# Sch_sensors.net
KiCad netlist of a schematic drawn in Altium Designer
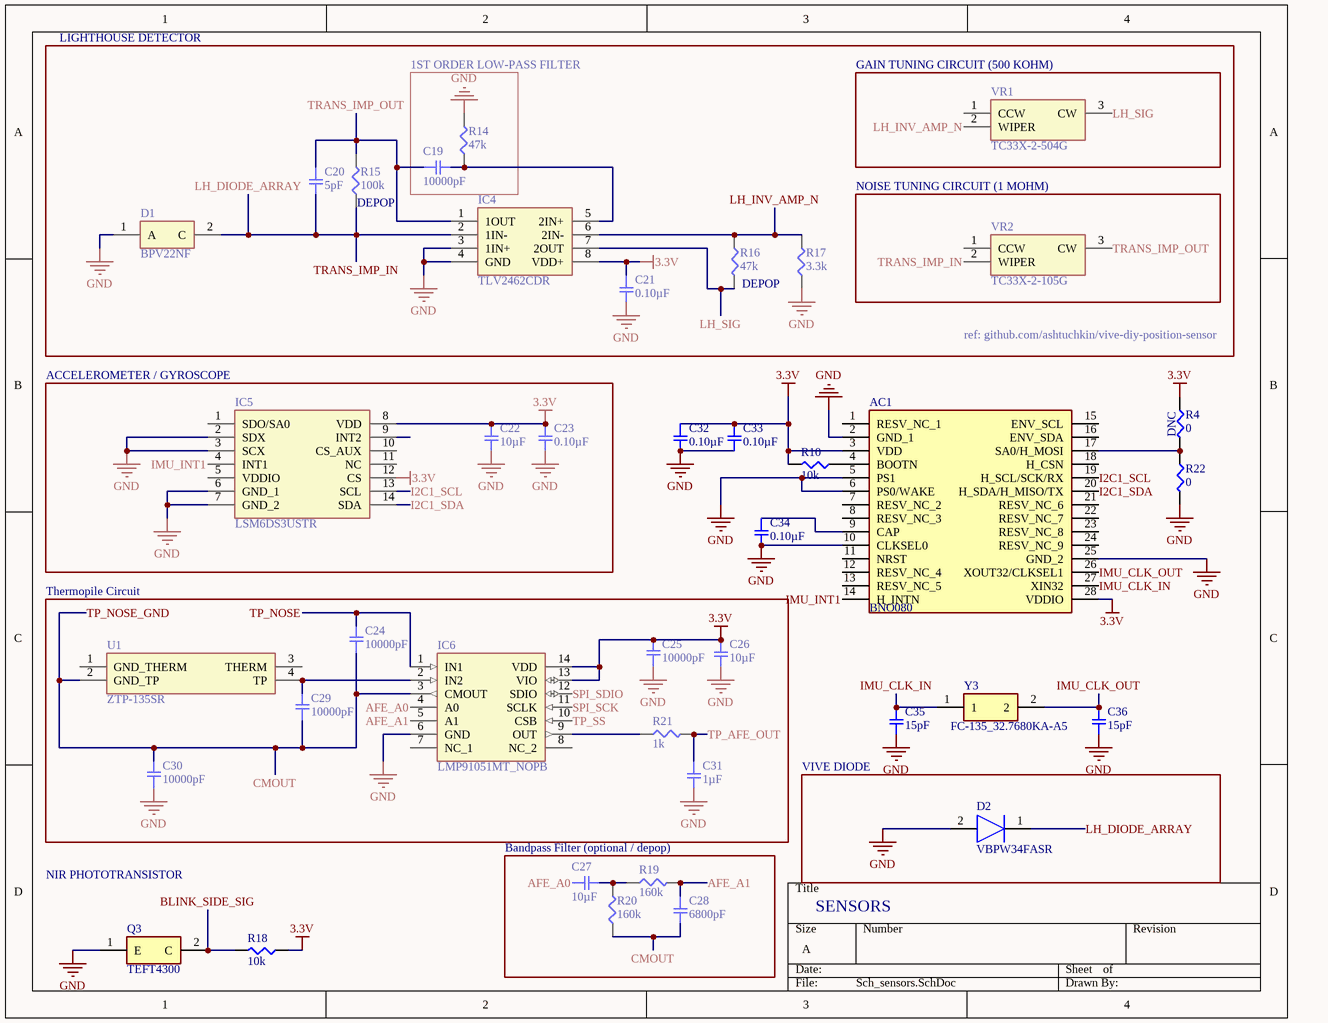
[diagram p0: Sch_sensors.SchDoc]

(export (version "E")
  (design (tool "Eeschema 10.0.6"))
  (components
    (comp (ref "AC1")
      (value "BNO080")
      (footprint "SamacSys:BNO080")
      (description "Accelerometer")
      (libsource (lib "*") (part "BNO080"))
    )
    (comp (ref "C19")
      (value "10000pF")
      (footprint "SMD-0402C")
      (description "CAP CER 10000PF 50V X7R 0402")
      (fields
        (field (name "DIGI-KEY PART NUMBER") "490-4762-1-ND")
        (field (name "PART NUMBER") "GCM155R71H103KA55D")
      )
      (libsource (lib "capacitor_murata_0402") (part "GCM155R71H103KA55D"))
    )
    (comp (ref "C20")
      (value "5pF")
      (footprint "SMD-0402C")
      (description "CAP CER 5PF 50V NP0 0402")
      (fields
        (field (name "DIGI-KEY PART NUMBER") "490-8103-1-ND")
        (field (name "PART NUMBER") "GJM1555C1H5R0BB01D")
      )
      (libsource (lib "capacitor_murata_0402") (part "GJM1555C1H5R0BB01D"))
    )
    (comp (ref "C21")
      (value "0.10µF")
      (footprint "SMD-0402C")
      (description "CAP CER 0.1UF 16V X7R 0402")
      (fields
        (field (name "DIGI-KEY PART NUMBER") "490-4759-1-ND")
        (field (name "PART NUMBER") "GCM155R71C104KA55D")
      )
      (libsource (lib "capacitor_murata_0402") (part "GCM155R71C104KA55D"))
    )
    (comp (ref "C22")
      (value "10µF")
      (footprint "SMD-0402C")
      (description "CAP CER 10UF 6.3V X5R 0402")
      (fields
        (field (name "DIGI-KEY PART NUMBER") "490-13211-1-ND")
        (field (name "PART NUMBER") "GRJ155R60J106ME11D")
      )
      (libsource (lib "capacitor_murata_0402") (part "GRJ155R60J106ME11D"))
    )
    (comp (ref "C23")
      (value "0.10µF")
      (footprint "SMD-0402C")
      (description "CAP CER 0.1UF 16V X7R 0402")
      (fields
        (field (name "DIGI-KEY PART NUMBER") "490-4759-1-ND")
        (field (name "PART NUMBER") "GCM155R71C104KA55D")
      )
      (libsource (lib "capacitor_murata_0402") (part "GCM155R71C104KA55D"))
    )
    (comp (ref "C24")
      (value "10000pF")
      (footprint "SMD-0402C")
      (description "CAP CER 10000PF 50V X7R 0402")
      (fields
        (field (name "DIGI-KEY PART NUMBER") "490-4762-1-ND")
        (field (name "PART NUMBER") "GCM155R71H103KA55D")
      )
      (libsource (lib "capacitor_murata_0402") (part "GCM155R71H103KA55D"))
    )
    (comp (ref "C25")
      (value "10000pF")
      (footprint "SMD-0402C")
      (description "CAP CER 10000PF 50V X7R 0402")
      (fields
        (field (name "DIGI-KEY PART NUMBER") "490-4762-1-ND")
        (field (name "PART NUMBER") "GCM155R71H103KA55D")
      )
      (libsource (lib "capacitor_murata_0402") (part "GCM155R71H103KA55D"))
    )
    (comp (ref "C26")
      (value "10µF")
      (footprint "SMD-0402C")
      (description "CAP CER 10UF 6.3V X5R 0402")
      (fields
        (field (name "DIGI-KEY PART NUMBER") "490-13211-1-ND")
        (field (name "PART NUMBER") "GRJ155R60J106ME11D")
      )
      (libsource (lib "capacitor_murata_0402") (part "GRJ155R60J106ME11D"))
    )
    (comp (ref "C27")
      (value "10µF")
      (footprint "SMD-0402C")
      (description "CAP CER 10UF 6.3V X5R 0402")
      (fields
        (field (name "DIGI-KEY PART NUMBER") "490-13211-1-ND")
        (field (name "PART NUMBER") "GRJ155R60J106ME11D")
      )
      (libsource (lib "capacitor_murata_0402") (part "GRJ155R60J106ME11D"))
    )
    (comp (ref "C28")
      (value "6800pF")
      (footprint "SMD-0402C")
      (description "CAP CER 6800PF 25V X7R 0402")
      (fields
        (field (name "DIGI-KEY PART NUMBER") "490-11422-1-ND")
        (field (name "PART NUMBER") "GRM155R71E682KA01J")
      )
      (libsource (lib "capacitor_murata_0402") (part "GRM155R71E682KA01J"))
    )
    (comp (ref "C29")
      (value "10000pF")
      (footprint "SMD-0402C")
      (description "CAP CER 10000PF 50V X7R 0402")
      (fields
        (field (name "DIGI-KEY PART NUMBER") "490-4762-1-ND")
        (field (name "PART NUMBER") "GCM155R71H103KA55D")
      )
      (libsource (lib "capacitor_murata_0402") (part "GCM155R71H103KA55D"))
    )
    (comp (ref "C30")
      (value "10000pF")
      (footprint "SMD-0402C")
      (description "CAP CER 10000PF 50V X7R 0402")
      (fields
        (field (name "DIGI-KEY PART NUMBER") "490-4762-1-ND")
        (field (name "PART NUMBER") "GCM155R71H103KA55D")
      )
      (libsource (lib "capacitor_murata_0402") (part "GCM155R71H103KA55D"))
    )
    (comp (ref "C31")
      (value "1µF")
      (footprint "SMD-0402C")
      (description "CAP CER 1UF 10V X7S 0402")
      (fields
        (field (name "DIGI-KEY PART NUMBER") "490-13409-1-ND")
        (field (name "PART NUMBER") "GCM155C71A105KE38D")
      )
      (libsource (lib "capacitor_murata_0402") (part "GCM155C71A105KE38D"))
    )
    (comp (ref "C32")
      (value "0.10µF")
      (footprint "CAPC1005X55N")
      (description "CAP CER 0.1UF 16V X7R 0402")
      (fields
        (field (name "DIGI-KEY PART NUMBER") "490-4759-1-ND")
        (field (name "PART NUMBER") "GCM155R71C104KA55D")
      )
      (libsource (lib "capacitor_murata_0402") (part "GCM155R71C104KA55D"))
    )
    (comp (ref "C33")
      (value "0.10µF")
      (footprint "CAPC1005X55N")
      (description "CAP CER 0.1UF 16V X7R 0402")
      (fields
        (field (name "DIGI-KEY PART NUMBER") "490-4759-1-ND")
        (field (name "PART NUMBER") "GCM155R71C104KA55D")
      )
      (libsource (lib "capacitor_murata_0402") (part "GCM155R71C104KA55D"))
    )
    (comp (ref "C34")
      (value "0.10µF")
      (footprint "CAPC1005X55N")
      (description "CAP CER 0.1UF 16V X7R 0402")
      (fields
        (field (name "DIGI-KEY PART NUMBER") "490-4759-1-ND")
        (field (name "PART NUMBER") "GCM155R71C104KA55D")
      )
      (libsource (lib "capacitor_murata_0402") (part "GCM155R71C104KA55D"))
    )
    (comp (ref "C35")
      (value "15pF")
      (footprint "CAPC1005X55N")
      (description "CAP CER 15PF 50V NP0 0402")
      (fields
        (field (name "DIGI-KEY PART NUMBER") "490-11147-1-ND")
        (field (name "PART NUMBER") "GCM1555C1H150JA16D")
      )
      (libsource (lib "capacitor_murata_0402") (part "GCM1555C1H150JA16D"))
    )
    (comp (ref "C36")
      (value "15pF")
      (footprint "CAPC1005X55N")
      (description "CAP CER 15PF 50V NP0 0402")
      (fields
        (field (name "DIGI-KEY PART NUMBER") "490-11147-1-ND")
        (field (name "PART NUMBER") "GCM1555C1H150JA16D")
      )
      (libsource (lib "capacitor_murata_0402") (part "GCM1555C1H150JA16D"))
    )
    (comp (ref "D1")
      (value "BPV22NF")
      (footprint "SamacSys:TO254P510X450X920-2P")
      (description "Diode")
      (fields (field (name "MOUSER PART NUMBER") "782-BPV22NF") (field (name "RS PART NUMBER") "6997604P"))
      (libsource (lib "*") (part "BPV22NF"))
    )
    (comp (ref "D2")
      (value "VBPW34FASR")
      (footprint "VBPW34FASR")
      (description "Diode")
      (fields (field (name "MOUSER PART NUMBER") "782-VBPW34FASR") (field (name "RS PART NUMBER") "7689401"))
      (libsource (lib "*") (part "VBPW34FASR"))
    )
    (comp (ref "IC4")
      (value "TLV2462CDR")
      (footprint "SamacSys:SOIC127P600X175-8N")
      (description "Integrated Circuit")
      (fields (field (name "MOUSER PART NUMBER") "595-TLV2462CDR") (field (name "RS PART NUMBER") "6610379"))
      (libsource (lib "*") (part "TLV2462CDR"))
    )
    (comp (ref "IC5")
      (value "LSM6DS3USTR")
      (footprint "SamacSys:LGA-14(2.5X3X0.86)")
      (description "Integrated Circuit")
      (fields (field (name "MOUSER PART NUMBER") "511-LSM6DS3USTR"))
      (libsource (lib "*") (part "LSM6DS3USTR"))
    )
    (comp (ref "IC6")
      (value "LMP91051MT_NOPB")
      (footprint "SamacSys:SOP65P640X120-14N")
      (description "Integrated Circuit")
      (fields
        (field (name "MANUFACTURER_PART_NUMBER") "LMP91051MT/NOPB")
        (field (name "MOUSER PART NUMBER") "595-LMP91051MT/NOPB")
      )
      (libsource (lib "*") (part "LMP91051MT_NOPB"))
    )
    (comp (ref "Q3")
      (value "TEFT4300")
      (footprint "SamacSys:TEFT4300")
      (description "Transistor")
      (fields (field (name "MOUSER PART NUMBER") "782-TEFT4300") (field (name "RS PART NUMBER") "7082731P"))
      (libsource (lib "*") (part "TEFT4300"))
    )
    (comp (ref "R4")
      (value "0")
      (footprint "SMD-0402-RES")
      (description "RES SMD 0K OHM 5% 1/10W 0402")
      (fields (field (name "PART NUMBER") "ERJ-2GEJ103X") (field (name "DIGI-KEY PART NUMBER") "P10KJCT-ND"))
      (libsource (lib "Panasonic_ERJ_0402") (part "ERJ-2GEJ103X"))
    )
    (comp (ref "R10")
      (value "10k")
      (footprint "SMD-0402-RES")
      (description "RES SMD 10K OHM 5% 1/10W 0402")
      (fields (field (name "PART NUMBER") "ERJ-2GEJ103X") (field (name "DIGI-KEY PART NUMBER") "P10KJCT-ND"))
      (libsource (lib "Panasonic_ERJ_0402") (part "ERJ-2GEJ103X"))
    )
    (comp (ref "R14")
      (value "47k")
      (footprint "SMD-0402-RES")
      (description "RES SMD 47K OHM 5% 1/10W 0402")
      (fields (field (name "PART NUMBER") "ERJ-2GEJ473X") (field (name "DIGI-KEY PART NUMBER") "P47KJCT-ND"))
      (libsource (lib "Panasonic_ERJ_0402") (part "ERJ-2GEJ473X"))
    )
    (comp (ref "R15")
      (value "100k")
      (footprint "SMD-0402-RES")
      (description "RES SMD 100K OHM 5% 1/10W 0402")
      (fields (field (name "PART NUMBER") "ERJ-2GEJ104X") (field (name "DIGI-KEY PART NUMBER") "P100KJCT-ND"))
      (libsource (lib "Panasonic_ERJ_0402") (part "ERJ-2GEJ104X"))
    )
    (comp (ref "R16")
      (value "47k")
      (footprint "SMD-0402-RES")
      (description "RES SMD 47K OHM 5% 1/10W 0402")
      (fields (field (name "PART NUMBER") "ERJ-2GEJ473X") (field (name "DIGI-KEY PART NUMBER") "P47KJCT-ND"))
      (libsource (lib "Panasonic_ERJ_0402") (part "ERJ-2GEJ473X"))
    )
    (comp (ref "R17")
      (value "3.3k")
      (footprint "SMD-0402-RES")
      (description "RES SMD 3.3K OHM 5% 1/10W 0402")
      (fields (field (name "PART NUMBER") "ERJ-2GEJ332X") (field (name "DIGI-KEY PART NUMBER") "P3.3KJCT-ND"))
      (libsource (lib "Panasonic_ERJ_0402") (part "ERJ-2GEJ332X"))
    )
    (comp (ref "R18")
      (value "10k")
      (footprint "SMD-0402-RES")
      (description "RES SMD 10K OHM 5% 1/10W 0402")
      (fields (field (name "PART NUMBER") "ERJ-2GEJ103X") (field (name "DIGI-KEY PART NUMBER") "P10KJCT-ND"))
      (libsource (lib "Panasonic_ERJ_0402") (part "ERJ-2GEJ103X"))
    )
    (comp (ref "R19")
      (value "160k")
      (footprint "SMD-0402-RES")
      (description "RES SMD 160K OHM 5% 1/10W 0402")
      (fields (field (name "PART NUMBER") "ERJ-2GEJ164X") (field (name "DIGI-KEY PART NUMBER") "P160KJCT-ND"))
      (libsource (lib "Panasonic_ERJ_0402") (part "ERJ-2GEJ164X"))
    )
    (comp (ref "R20")
      (value "160k")
      (footprint "SMD-0402-RES")
      (description "RES SMD 160K OHM 5% 1/10W 0402")
      (fields (field (name "PART NUMBER") "ERJ-2GEJ164X") (field (name "DIGI-KEY PART NUMBER") "P160KJCT-ND"))
      (libsource (lib "Panasonic_ERJ_0402") (part "ERJ-2GEJ164X"))
    )
    (comp (ref "R21")
      (value "1k")
      (footprint "SMD-0402-RES")
      (description "RES SMD 1K OHM 5% 1/10W 0402")
      (fields (field (name "PART NUMBER") "ERJ-2GEJ102X") (field (name "DIGI-KEY PART NUMBER") "P1.0KJCT-ND"))
      (libsource (lib "Panasonic_ERJ_0402") (part "ERJ-2GEJ102X"))
    )
    (comp (ref "R22")
      (value "0")
      (footprint "SMD-0402-RES")
      (description "RES SMD 0K OHM 5% 1/10W 0402")
      (fields (field (name "PART NUMBER") "ERJ-2GEJ103X") (field (name "DIGI-KEY PART NUMBER") "P10KJCT-ND"))
      (libsource (lib "Panasonic_ERJ_0402") (part "ERJ-2GEJ103X"))
    )
    (comp (ref "U1")
      (value "ZTP-135SR")
      (footprint "SamacSys:ZTP-135SR")
      (description "Undefined or Miscellaneous")
      (fields (field (name "MOUSER PART NUMBER") "527-ZTP-135SR"))
      (libsource (lib "SamacSys") (part "ZTP-135SR"))
    )
    (comp (ref "VR1")
      (value "TC33X-2-504G")
      (footprint "SamacSys:TC33X-2_1")
      (description "Variable Resistor")
      (fields (field (name "MOUSER PART NUMBER") "652-TC33X-2-504G"))
      (libsource (lib "*") (part "TC33X-2-504G"))
    )
    (comp (ref "VR2")
      (value "TC33X-2-105G")
      (footprint "SamacSys:TC33X-2_1")
      (description "Variable Resistor")
      (fields (field (name "MOUSER PART NUMBER") "652-TC33X-2-105G"))
      (libsource (lib "*") (part "TC33X-2-504G"))
    )
    (comp (ref "Y3")
      (value "FC-135_32.7680KA-A5")
      (footprint "SamacSys:FC135327680KAAG0")
      (description "Crystal or Oscillator")
      (fields
        (field (name "MANUFACTURER_PART_NUMBER") "FC-135 32.7680KA-A5")
        (field (name "MOUSER PART NUMBER") "732-FC135-32.76KAA3")
      )
      (libsource (lib "*") (part "FC-135_32.7680KA-A3"))
    )
  )
  (nets
    (net (code "1") (name "/AFE_A0") (class "Default")
      (node (ref "C27") (pin "1") (pinfunction "1_1") (pintype "passive"))
      (node (ref "IC6") (pin "4") (pinfunction "A0_4") (pintype "passive"))
    )
    (net (code "2") (name "/AFE_A1") (class "Default")
      (node (ref "C28") (pin "1") (pinfunction "1_1") (pintype "passive"))
      (node (ref "IC6") (pin "5") (pinfunction "A1_5") (pintype "passive"))
      (node (ref "R19") (pin "2") (pinfunction "2_2") (pintype "passive"))
    )
    (net (code "3") (name "/BLINK_SIDE_SIG") (class "Default")
      (node (ref "Q3") (pin "2") (pinfunction "C_2") (pintype "passive"))
      (node (ref "R18") (pin "2") (pinfunction "2_2") (pintype "passive"))
    )
    (net (code "4") (name "/CMOUT") (class "Default")
      (node (ref "C24") (pin "1") (pinfunction "1_1") (pintype "passive"))
      (node (ref "C28") (pin "2") (pinfunction "2_2") (pintype "passive"))
      (node (ref "C29") (pin "1") (pinfunction "1_1") (pintype "passive"))
      (node (ref "C30") (pin "2") (pinfunction "2_2") (pintype "passive"))
      (node (ref "IC6") (pin "3") (pinfunction "CMOUT_3") (pintype "output"))
      (node (ref "R20") (pin "1") (pinfunction "1_1") (pintype "passive"))
      (node (ref "U1") (pin "2") (pinfunction "GND_TP_2") (pintype "passive"))
    )
    (net (code "5") (name "/I2C1_SCL") (class "Default")
      (node (ref "AC1") (pin "19") (pinfunction "H_SCL/SCK/RX_19") (pintype "passive"))
      (node (ref "IC5") (pin "13") (pinfunction "SCL_13") (pintype "passive"))
    )
    (net (code "6") (name "/I2C1_SDA") (class "Default")
      (node (ref "AC1") (pin "20") (pinfunction "H_SDA/H_MISO/TX_20") (pintype "passive"))
      (node (ref "IC5") (pin "14") (pinfunction "SDA_14") (pintype "passive"))
    )
    (net (code "7") (name "/IMU_CLK_IN") (class "Default")
      (node (ref "AC1") (pin "27") (pinfunction "XIN32_27") (pintype "passive"))
      (node (ref "C35") (pin "1") (pinfunction "1_1") (pintype "passive"))
      (node (ref "Y3") (pin "1") (pinfunction "1_1") (pintype "passive"))
    )
    (net (code "8") (name "/IMU_CLK_OUT") (class "Default")
      (node (ref "AC1") (pin "26") (pinfunction "XOUT32/CLKSEL1_26") (pintype "passive"))
      (node (ref "C36") (pin "1") (pinfunction "1_1") (pintype "passive"))
      (node (ref "Y3") (pin "2") (pinfunction "2_2") (pintype "passive"))
    )
    (net (code "9") (name "/IMU_INT1") (class "Default")
      (node (ref "AC1") (pin "14") (pinfunction "H_INTN_14") (pintype "passive"))
      (node (ref "IC5") (pin "4") (pinfunction "INT1_4") (pintype "passive"))
    )
    (net (code "10") (name "/LH_DIODE_ARRAY") (class "Default")
      (node (ref "C20") (pin "2") (pinfunction "2_2") (pintype "passive"))
      (node (ref "D1") (pin "2") (pinfunction "C_2") (pintype "passive"))
      (node (ref "D2") (pin "1") (pinfunction "A_1") (pintype "passive"))
      (node (ref "IC4") (pin "2") (pinfunction "1IN-_2") (pintype "passive"))
      (node (ref "R15") (pin "1") (pinfunction "1_1") (pintype "passive"))
      (node (ref "VR2") (pin "2") (pinfunction "WIPER_2") (pintype "passive"))
    )
    (net (code "11") (name "/LH_INV_AMP_N") (class "Default")
      (node (ref "IC4") (pin "6") (pinfunction "2IN-_6") (pintype "passive"))
      (node (ref "R16") (pin "1") (pinfunction "1_1") (pintype "passive"))
      (node (ref "R17") (pin "2") (pinfunction "2_2") (pintype "passive"))
      (node (ref "VR1") (pin "2") (pinfunction "WIPER_2") (pintype "passive"))
    )
    (net (code "12") (name "/LH_SIG") (class "Default")
      (node (ref "IC4") (pin "7") (pinfunction "2OUT_7") (pintype "passive"))
      (node (ref "R16") (pin "2") (pinfunction "2_2") (pintype "passive"))
      (node (ref "VR1") (pin "3") (pinfunction "CW_3") (pintype "passive"))
    )
    (net (code "13") (name "/SPI_SCK") (class "Default")
      (node (ref "IC6") (pin "11") (pinfunction "SCLK_11") (pintype "input"))
    )
    (net (code "14") (name "/SPI_SDIO") (class "Default")
      (node (ref "IC6") (pin "12") (pinfunction "SDIO_12") (pintype "bidirectional"))
    )
    (net (code "15") (name "/TP_AFE_OUT") (class "Default")
      (node (ref "C31") (pin "1") (pinfunction "1_1") (pintype "passive"))
      (node (ref "R21") (pin "2") (pinfunction "2_2") (pintype "passive"))
    )
    (net (code "16") (name "/TP_NOSE") (class "Default")
      (node (ref "C24") (pin "2") (pinfunction "2_2") (pintype "passive"))
      (node (ref "IC6") (pin "1") (pinfunction "IN1_1") (pintype "input"))
    )
    (net (code "17") (name "/TP_SS") (class "Default")
      (node (ref "IC6") (pin "10") (pinfunction "CSB_10") (pintype "input"))
    )
    (net (code "18") (name "/TRANS_IMP_OUT") (class "Default")
      (node (ref "C19") (pin "1") (pinfunction "1_1") (pintype "passive"))
      (node (ref "C20") (pin "1") (pinfunction "1_1") (pintype "passive"))
      (node (ref "IC4") (pin "1") (pinfunction "1OUT_1") (pintype "passive"))
      (node (ref "R15") (pin "2") (pinfunction "2_2") (pintype "passive"))
      (node (ref "VR2") (pin "3") (pinfunction "CW_3") (pintype "passive"))
    )
    (net (code "19") (name "3.3V") (class "Default")
      (node (ref "AC1") (pin "28") (pinfunction "VDDIO_28") (pintype "passive"))
      (node (ref "AC1") (pin "3") (pinfunction "VDD_3") (pintype "passive"))
      (node (ref "C21") (pin "1") (pinfunction "1_1") (pintype "passive"))
      (node (ref "C22") (pin "1") (pinfunction "1_1") (pintype "passive"))
      (node (ref "C23") (pin "1") (pinfunction "1_1") (pintype "passive"))
      (node (ref "C25") (pin "2") (pinfunction "2_2") (pintype "passive"))
      (node (ref "C26") (pin "1") (pinfunction "1_1") (pintype "passive"))
      (node (ref "C32") (pin "1") (pinfunction "1_1") (pintype "passive"))
      (node (ref "C33") (pin "1") (pinfunction "1_1") (pintype "passive"))
      (node (ref "IC4") (pin "8") (pinfunction "VDD+_8") (pintype "passive"))
      (node (ref "IC5") (pin "12") (pinfunction "CS_12") (pintype "passive"))
      (node (ref "IC5") (pin "8") (pinfunction "VDD_8") (pintype "passive"))
      (node (ref "IC6") (pin "13") (pinfunction "VIO_13") (pintype "bidirectional"))
      (node (ref "IC6") (pin "14") (pinfunction "VDD_14") (pintype "power_in"))
      (node (ref "R10") (pin "2") (pinfunction "2_2") (pintype "passive"))
      (node (ref "R18") (pin "1") (pinfunction "1_1") (pintype "passive"))
      (node (ref "R4") (pin "1") (pinfunction "1_1") (pintype "passive"))
    )
    (net (code "20") (name "GND") (class "Default")
      (node (ref "AC1") (pin "10") (pinfunction "CLKSEL0_10") (pintype "passive"))
      (node (ref "AC1") (pin "2") (pinfunction "GND_1_2") (pintype "passive"))
      (node (ref "AC1") (pin "25") (pinfunction "GND_2_25") (pintype "passive"))
      (node (ref "AC1") (pin "5") (pinfunction "PS1_5") (pintype "passive"))
      (node (ref "AC1") (pin "6") (pinfunction "PS0/WAKE_6") (pintype "passive"))
      (node (ref "C21") (pin "2") (pinfunction "2_2") (pintype "passive"))
      (node (ref "C22") (pin "2") (pinfunction "2_2") (pintype "passive"))
      (node (ref "C23") (pin "2") (pinfunction "2_2") (pintype "passive"))
      (node (ref "C25") (pin "1") (pinfunction "1_1") (pintype "passive"))
      (node (ref "C26") (pin "2") (pinfunction "2_2") (pintype "passive"))
      (node (ref "C30") (pin "1") (pinfunction "1_1") (pintype "passive"))
      (node (ref "C31") (pin "2") (pinfunction "2_2") (pintype "passive"))
      (node (ref "C32") (pin "2") (pinfunction "2_2") (pintype "passive"))
      (node (ref "C33") (pin "2") (pinfunction "2_2") (pintype "passive"))
      (node (ref "C34") (pin "2") (pinfunction "2_2") (pintype "passive"))
      (node (ref "C35") (pin "2") (pinfunction "2_2") (pintype "passive"))
      (node (ref "C36") (pin "2") (pinfunction "2_2") (pintype "passive"))
      (node (ref "D1") (pin "1") (pinfunction "A_1") (pintype "passive"))
      (node (ref "D2") (pin "2") (pinfunction "K_2") (pintype "passive"))
      (node (ref "IC4") (pin "3") (pinfunction "1IN+_3") (pintype "passive"))
      (node (ref "IC4") (pin "4") (pinfunction "GND_4") (pintype "passive"))
      (node (ref "IC5") (pin "2") (pinfunction "SDX_2") (pintype "passive"))
      (node (ref "IC5") (pin "3") (pinfunction "SCX_3") (pintype "passive"))
      (node (ref "IC5") (pin "6") (pinfunction "GND_1_6") (pintype "passive"))
      (node (ref "IC5") (pin "7") (pinfunction "GND_2_7") (pintype "passive"))
      (node (ref "IC6") (pin "6") (pinfunction "GND_6") (pintype "power_in"))
      (node (ref "Q3") (pin "1") (pinfunction "E_1") (pintype "passive"))
      (node (ref "R14") (pin "2") (pinfunction "2_2") (pintype "passive"))
      (node (ref "R17") (pin "1") (pinfunction "1_1") (pintype "passive"))
      (node (ref "R22") (pin "2") (pinfunction "2_2") (pintype "passive"))
    )
    (net (code "21") (name "Net-(AC1-BOOTN)") (class "Default")
      (node (ref "AC1") (pin "4") (pinfunction "BOOTN_4") (pintype "passive"))
      (node (ref "R10") (pin "1") (pinfunction "1_1") (pintype "passive"))
    )
    (net (code "22") (name "Net-(AC1-CAP)") (class "Default")
      (node (ref "AC1") (pin "9") (pinfunction "CAP_9") (pintype "passive"))
      (node (ref "C34") (pin "1") (pinfunction "1_1") (pintype "passive"))
    )
    (net (code "23") (name "Net-(AC1-SA0{slash}H_MOSI)") (class "Default")
      (node (ref "AC1") (pin "17") (pinfunction "SA0/H_MOSI_17") (pintype "passive"))
      (node (ref "R22") (pin "1") (pinfunction "1_1") (pintype "passive"))
      (node (ref "R4") (pin "2") (pinfunction "2_2") (pintype "passive"))
    )
    (net (code "24") (name "Net-(C27-Pad2)") (class "Default")
      (node (ref "C27") (pin "2") (pinfunction "2_2") (pintype "passive"))
      (node (ref "R19") (pin "1") (pinfunction "1_1") (pintype "passive"))
      (node (ref "R20") (pin "2") (pinfunction "2_2") (pintype "passive"))
    )
    (net (code "25") (name "Net-(IC4-2IN+)") (class "Default")
      (node (ref "C19") (pin "2") (pinfunction "2_2") (pintype "passive"))
      (node (ref "IC4") (pin "5") (pinfunction "2IN+_5") (pintype "passive"))
      (node (ref "R14") (pin "1") (pinfunction "1_1") (pintype "passive"))
    )
    (net (code "26") (name "Net-(IC6-IN2)") (class "Default")
      (node (ref "C29") (pin "2") (pinfunction "2_2") (pintype "passive"))
      (node (ref "IC6") (pin "2") (pinfunction "IN2_2") (pintype "input"))
      (node (ref "U1") (pin "4") (pinfunction "TP_4") (pintype "passive"))
    )
    (net (code "27") (name "Net-(IC6-OUT)") (class "Default")
      (node (ref "IC6") (pin "9") (pinfunction "OUT_9") (pintype "output"))
      (node (ref "R21") (pin "1") (pinfunction "1_1") (pintype "passive"))
    )
    (net (code "28") (name "unconnected-(AC1-ENV_SCL-Pad15)") (class "Default")
      (node (ref "AC1") (pin "15") (pinfunction "ENV_SCL_15") (pintype "passive"))
    )
    (net (code "29") (name "unconnected-(AC1-ENV_SDA-Pad16)") (class "Default")
      (node (ref "AC1") (pin "16") (pinfunction "ENV_SDA_16") (pintype "passive"))
    )
    (net (code "30") (name "unconnected-(AC1-H_CSN-Pad18)") (class "Default")
      (node (ref "AC1") (pin "18") (pinfunction "H_CSN_18") (pintype "passive"))
    )
    (net (code "31") (name "unconnected-(AC1-NRST-Pad11)") (class "Default")
      (node (ref "AC1") (pin "11") (pinfunction "NRST_11") (pintype "passive"))
    )
    (net (code "32") (name "unconnected-(AC1-RESV_NC_1-Pad1)") (class "Default")
      (node (ref "AC1") (pin "1") (pinfunction "RESV_NC_1_1") (pintype "passive"))
    )
    (net (code "33") (name "unconnected-(AC1-RESV_NC_2-Pad7)") (class "Default")
      (node (ref "AC1") (pin "7") (pinfunction "RESV_NC_2_7") (pintype "passive"))
    )
    (net (code "34") (name "unconnected-(AC1-RESV_NC_3-Pad8)") (class "Default")
      (node (ref "AC1") (pin "8") (pinfunction "RESV_NC_3_8") (pintype "passive"))
    )
    (net (code "35") (name "unconnected-(AC1-RESV_NC_4-Pad12)") (class "Default")
      (node (ref "AC1") (pin "12") (pinfunction "RESV_NC_4_12") (pintype "passive"))
    )
    (net (code "36") (name "unconnected-(AC1-RESV_NC_5-Pad13)") (class "Default")
      (node (ref "AC1") (pin "13") (pinfunction "RESV_NC_5_13") (pintype "passive"))
    )
    (net (code "37") (name "unconnected-(AC1-RESV_NC_6-Pad21)") (class "Default")
      (node (ref "AC1") (pin "21") (pinfunction "RESV_NC_6_21") (pintype "passive"))
    )
    (net (code "38") (name "unconnected-(AC1-RESV_NC_7-Pad22)") (class "Default")
      (node (ref "AC1") (pin "22") (pinfunction "RESV_NC_7_22") (pintype "passive"))
    )
    (net (code "39") (name "unconnected-(AC1-RESV_NC_8-Pad23)") (class "Default")
      (node (ref "AC1") (pin "23") (pinfunction "RESV_NC_8_23") (pintype "passive"))
    )
    (net (code "40") (name "unconnected-(AC1-RESV_NC_9-Pad24)") (class "Default")
      (node (ref "AC1") (pin "24") (pinfunction "RESV_NC_9_24") (pintype "passive"))
    )
    (net (code "41") (name "unconnected-(IC5-CS_AUX-Pad10)") (class "Default")
      (node (ref "IC5") (pin "10") (pinfunction "CS_AUX_10") (pintype "passive"))
    )
    (net (code "42") (name "unconnected-(IC5-INT2-Pad9)") (class "Default")
      (node (ref "IC5") (pin "9") (pinfunction "INT2_9") (pintype "passive"))
    )
    (net (code "43") (name "unconnected-(IC5-NC-Pad11)") (class "Default")
      (node (ref "IC5") (pin "11") (pinfunction "NC_11") (pintype "passive"))
    )
    (net (code "44") (name "unconnected-(IC5-SDO{slash}SA0-Pad1)") (class "Default")
      (node (ref "IC5") (pin "1") (pinfunction "SDO/SA0_1") (pintype "passive"))
    )
    (net (code "45") (name "unconnected-(IC5-VDDIO-Pad5)") (class "Default")
      (node (ref "IC5") (pin "5") (pinfunction "VDDIO_5") (pintype "passive"))
    )
    (net (code "46") (name "unconnected-(IC6-NC_1-Pad7)") (class "Default")
      (node (ref "IC6") (pin "7") (pinfunction "NC_1_7") (pintype "passive"))
    )
    (net (code "47") (name "unconnected-(IC6-NC_2-Pad8)") (class "Default")
      (node (ref "IC6") (pin "8") (pinfunction "NC_2_8") (pintype "passive"))
    )
    (net (code "48") (name "unconnected-(U1-GND_THERM-Pad1)") (class "Default")
      (node (ref "U1") (pin "1") (pinfunction "GND_THERM_1") (pintype "passive"))
    )
    (net (code "49") (name "unconnected-(U1-THERM-Pad3)") (class "Default")
      (node (ref "U1") (pin "3") (pinfunction "THERM_3") (pintype "passive"))
    )
    (net (code "50") (name "unconnected-(VR1-CCW-Pad1)") (class "Default")
      (node (ref "VR1") (pin "1") (pinfunction "CCW_1") (pintype "passive"))
    )
    (net (code "51") (name "unconnected-(VR2-CCW-Pad1)") (class "Default")
      (node (ref "VR2") (pin "1") (pinfunction "CCW_1") (pintype "passive"))
    )
  )
)
